# POE_RS-485.net
KiCad netlist of a schematic drawn in EAGLE
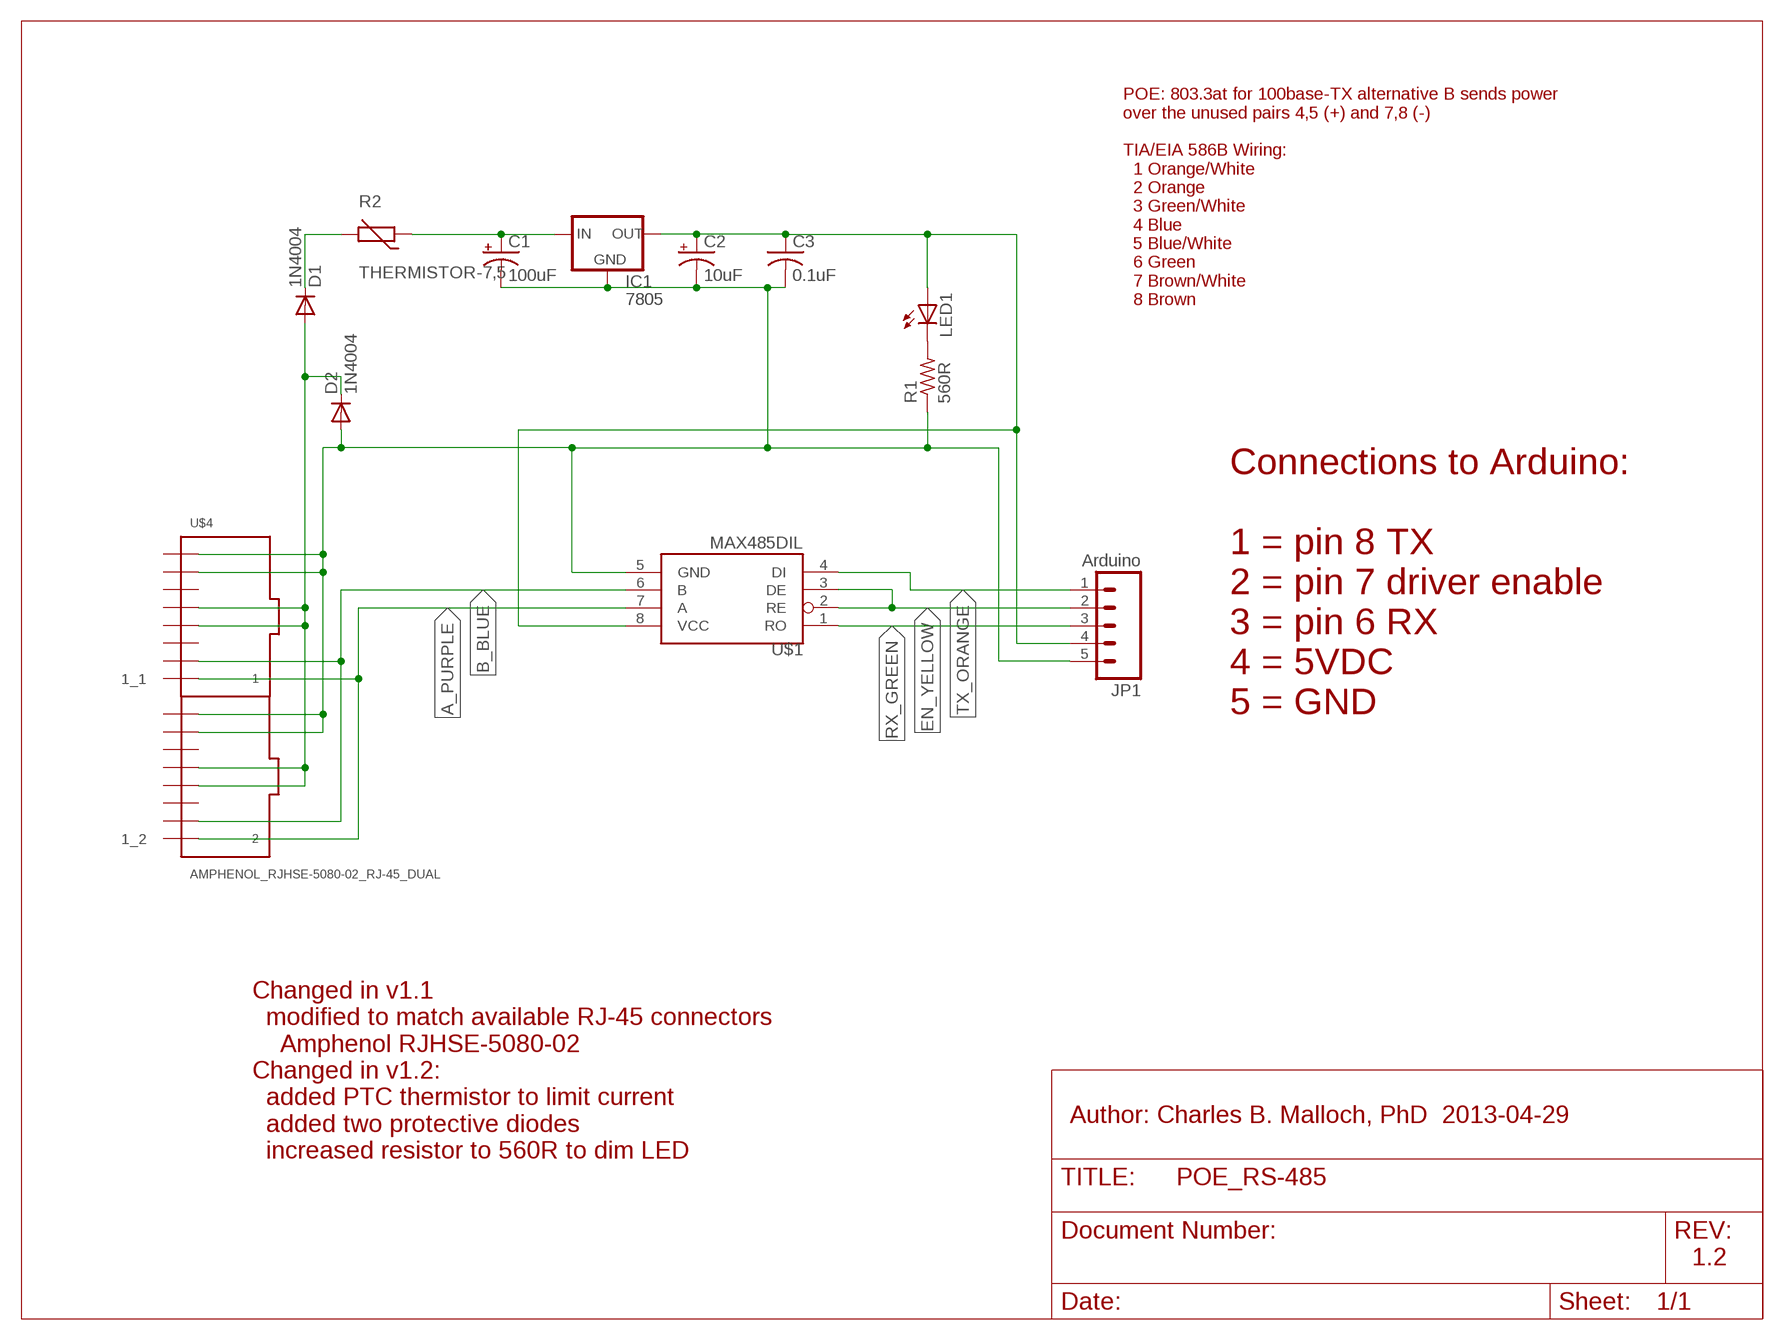
[diagram p0: schematic, sheet 1]

(export (version "E")
  (design (tool "Eeschema 10.0.6"))
  (components
    (comp (ref "C1")
      (value "100uF")
      (footprint "eagle-import:TT2D7")
      (libsource (lib "eagle-import") (part "CPOL-USTT2D7"))
    )
    (comp (ref "C2")
      (value "10uF")
      (footprint "eagle-import:E1,8-4")
      (libsource (lib "eagle-import") (part "CPOL-USE1.8-4"))
    )
    (comp (ref "C3")
      (value "0.1uF")
      (footprint "eagle-import:C025-025X050")
      (libsource (lib "eagle-import") (part "C-US025-025X050"))
    )
    (comp (ref "D1")
      (value "1N4004")
      (footprint "eagle-import:DO41-10")
      (libsource (lib "eagle-import") (part "1N4004"))
    )
    (comp (ref "D2")
      (value "1N4004")
      (footprint "eagle-import:DO41-10")
      (libsource (lib "eagle-import") (part "1N4004"))
    )
    (comp (ref "IC1")
      (value "7805")
      (footprint "eagle-import:TO-220-ALT")
      (libsource (lib "eagle-import") (part "V_REG_78XX-TO-220"))
    )
    (comp (ref "JP1")
      (value "Arduino")
      (footprint "eagle-import:1X05_LOCK_LONGPADS")
      (libsource (lib "eagle-import") (part "M05LOCK_LONGPADS"))
    )
    (comp (ref "LED1")
      (value "LED3MM")
      (footprint "eagle-import:LED3MM")
      (libsource (lib "eagle-import") (part "LED3MM"))
    )
    (comp (ref "R1")
      (value "560R")
      (footprint "eagle-import:0204_7")
      (libsource (lib "eagle-import") (part "R-US_0204/7"))
    )
    (comp (ref "R2")
      (value "THERMISTOR-7,5")
      (footprint "eagle-import:R-7,5")
      (libsource (lib "eagle-import") (part "THERMISTOR-7,5"))
    )
    (comp (ref "U$1")
      (value "MAX485DIL")
      (footprint "eagle-import:DIL08")
      (libsource (lib "eagle-import") (part "MAX485DIL"))
    )
    (comp (ref "U$4")
      (value "AMPHENOL_RJHSE-5080-02_RJ-45_DUAL")
      (footprint "eagle-import:AMPHENOL_RJHSE-5080-02")
      (libsource (lib "eagle-import") (part "AMPHENOL_RJHSE-5080-02_RJ-45_DUAL"))
    )
  )
  (nets
    (net (code "1") (name "A_PURPLE") (class "Default")
      (node (ref "U$1") (pin "7") (pinfunction "A_7") (pintype "bidirectional"))
      (node (ref "U$4") (pin "TX_D1+_2") (pinfunction "1_2_TX_D1+_2") (pintype "bidirectional"))
      (node (ref "U$4") (pin "TX_DI+_1") (pinfunction "1_1_TX_DI+_1") (pintype "bidirectional"))
    )
    (net (code "2") (name "B_BLUE") (class "Default")
      (node (ref "U$1") (pin "6") (pinfunction "B_6") (pintype "bidirectional"))
      (node (ref "U$4") (pin "TX_D1-_2") (pinfunction "2_2_TX_D1-_2") (pintype "bidirectional"))
      (node (ref "U$4") (pin "TX_DI-_1") (pinfunction "2_1_TX_DI-_1") (pintype "bidirectional"))
    )
    (net (code "3") (name "EN_YELLOW") (class "Default")
      (node (ref "JP1") (pin "2") (pinfunction "2_2") (pintype "passive"))
      (node (ref "U$1") (pin "2") (pinfunction "RE_2") (pintype "bidirectional"))
      (node (ref "U$1") (pin "3") (pinfunction "DE_3") (pintype "bidirectional"))
    )
    (net (code "4") (name "Net-(C1-Pad+)") (class "Default")
      (node (ref "C1") (pin "+") (pinfunction "+_+") (pintype "passive"))
      (node (ref "IC1") (pin "IN") (pinfunction "IN_IN") (pintype "input"))
      (node (ref "R2") (pin "1") (pinfunction "1_1") (pintype "passive"))
    )
    (net (code "5") (name "Net-(D1-PadC)") (class "Default")
      (node (ref "D1") (pin "C") (pinfunction "C_C") (pintype "passive"))
      (node (ref "R2") (pin "2") (pinfunction "2_2") (pintype "passive"))
    )
    (net (code "6") (name "Net-(LED1-C)") (class "Default")
      (node (ref "LED1") (pin "K") (pinfunction "C_K") (pintype "passive"))
      (node (ref "R1") (pin "2") (pinfunction "2_2") (pintype "passive"))
    )
    (net (code "7") (name "Net-(U$1-GND)") (class "Default")
      (node (ref "C1") (pin "-") (pinfunction "-_-") (pintype "passive"))
      (node (ref "C2") (pin "-") (pinfunction "-_-") (pintype "passive"))
      (node (ref "C3") (pin "2") (pinfunction "2_2") (pintype "passive"))
      (node (ref "D2") (pin "A") (pinfunction "A_A") (pintype "passive"))
      (node (ref "IC1") (pin "GND") (pinfunction "GND_GND") (pintype "input"))
      (node (ref "JP1") (pin "5") (pinfunction "5_5") (pintype "passive"))
      (node (ref "R1") (pin "1") (pinfunction "1_1") (pintype "passive"))
      (node (ref "U$1") (pin "5") (pinfunction "GND_5") (pintype "bidirectional"))
      (node (ref "U$4") (pin "POE-_1_1") (pinfunction "7_1_POE-_1_1") (pintype "bidirectional"))
      (node (ref "U$4") (pin "POE-_1_2") (pinfunction "7_2_POE-_1_2") (pintype "bidirectional"))
      (node (ref "U$4") (pin "POE-_2_1") (pinfunction "8_1_POE-_2_1") (pintype "bidirectional"))
      (node (ref "U$4") (pin "POE-_2_2") (pinfunction "8_2_POE-_2_2") (pintype "bidirectional"))
    )
    (net (code "8") (name "Net-(U$1-VCC)") (class "Default")
      (node (ref "C2") (pin "+") (pinfunction "+_+") (pintype "passive"))
      (node (ref "C3") (pin "1") (pinfunction "1_1") (pintype "passive"))
      (node (ref "IC1") (pin "OUT") (pinfunction "OUT_OUT") (pintype "output"))
      (node (ref "JP1") (pin "4") (pinfunction "4_4") (pintype "passive"))
      (node (ref "LED1") (pin "A") (pinfunction "A_A") (pintype "passive"))
      (node (ref "U$1") (pin "8") (pinfunction "VCC_8") (pintype "bidirectional"))
    )
    (net (code "9") (name "Net-(U$4-4_1)") (class "Default")
      (node (ref "D1") (pin "A") (pinfunction "A_A") (pintype "passive"))
      (node (ref "D2") (pin "C") (pinfunction "C_C") (pintype "passive"))
      (node (ref "U$4") (pin "POE+_1_1") (pinfunction "4_1_POE+_1_1") (pintype "bidirectional"))
      (node (ref "U$4") (pin "POE+_1_2") (pinfunction "4_2_POE+_1_2") (pintype "bidirectional"))
      (node (ref "U$4") (pin "POE+_2_1") (pinfunction "5_1_POE+_2_1") (pintype "bidirectional"))
      (node (ref "U$4") (pin "POE+_2_2") (pinfunction "5_2_POE+_2_2") (pintype "bidirectional"))
    )
    (net (code "10") (name "RX_GREEN") (class "Default")
      (node (ref "JP1") (pin "3") (pinfunction "3_3") (pintype "passive"))
      (node (ref "U$1") (pin "1") (pinfunction "RO_1") (pintype "bidirectional"))
    )
    (net (code "11") (name "TX_ORANGE") (class "Default")
      (node (ref "JP1") (pin "1") (pinfunction "1_1") (pintype "passive"))
      (node (ref "U$1") (pin "4") (pinfunction "DI_4") (pintype "bidirectional"))
    )
    (net (code "12") (name "unconnected-(U$4-3_1-PadRX_D2+_1)") (class "Default")
      (node (ref "U$4") (pin "RX_D2+_1") (pinfunction "3_1_RX_D2+_1") (pintype "bidirectional"))
    )
    (net (code "13") (name "unconnected-(U$4-3_2-PadRX_D2+_2)") (class "Default")
      (node (ref "U$4") (pin "RX_D2+_2") (pinfunction "3_2_RX_D2+_2") (pintype "bidirectional"))
    )
    (net (code "14") (name "unconnected-(U$4-6_1-PadRX_D2-_1)") (class "Default")
      (node (ref "U$4") (pin "RX_D2-_1") (pinfunction "6_1_RX_D2-_1") (pintype "bidirectional"))
    )
    (net (code "15") (name "unconnected-(U$4-6_2-PadRX_D2-_2)") (class "Default")
      (node (ref "U$4") (pin "RX_D2-_2") (pinfunction "6_2_RX_D2-_2") (pintype "bidirectional"))
    )
  )
)
